# display.net
KiCad netlist of a schematic drawn in Altium Designer
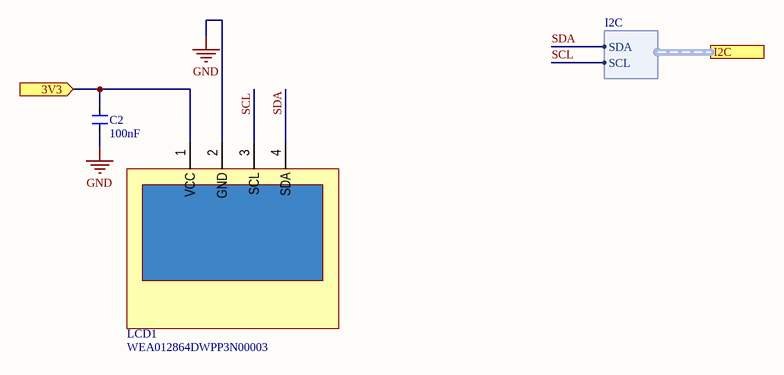
[diagram p0: display.SchDoc]

(export (version "E")
  (design (tool "Eeschema 10.0.6"))
  (components
    (comp (ref "C2")
      (value "100nF")
      (footprint "CAP0603")
      (description "Tolerance ±10%\nRated Voltage 50Vdc\nTemperature 0±30ppm/℃")
      (fields (field (name "PART NUMBER") "GCM188R71H104KA57J") (field (name "TOLERANCE") "10%"))
      (libsource (lib "Lib_Kam") (part "Capacitor"))
    )
    (comp (ref "LCD1")
      (value "WEA012864DWPP3N00003")
      (footprint "WEA012864DWPP3N00003")
      (description "OLED 0.96\" display, 128x64, white,  IC SSD1306BZ, I2C, 3v, -40...+80°С")
      (fields (field (name "MANUFACTURER") "Winstar"))
      (libsource (lib "Lib_Kam") (part "WEA012864DWPP3N00003"))
    )
  )
  (nets
    (net (code "2") (name "/3V3") (class "Default")
      (node (ref "C2") (pin "2") (pinfunction "2_2") (pintype "passive"))
      (node (ref "LCD1") (pin "1") (pinfunction "VCC_1") (pintype "passive"))
    )
    (net (code "3") (name "/SCL") (class "Default")
      (node (ref "LCD1") (pin "3") (pinfunction "SCL_3") (pintype "passive"))
    )
    (net (code "4") (name "/SDA") (class "Default")
      (node (ref "LCD1") (pin "4") (pinfunction "SDA_4") (pintype "passive"))
    )
    (net (code "6") (name "GND") (class "Default")
      (node (ref "C2") (pin "1") (pinfunction "2_1") (pintype "passive"))
      (node (ref "LCD1") (pin "2") (pinfunction "GND_2") (pintype "passive"))
    )
  )
)
